# Chov2_main.net
KiCad netlist of a schematic drawn in Altium Designer
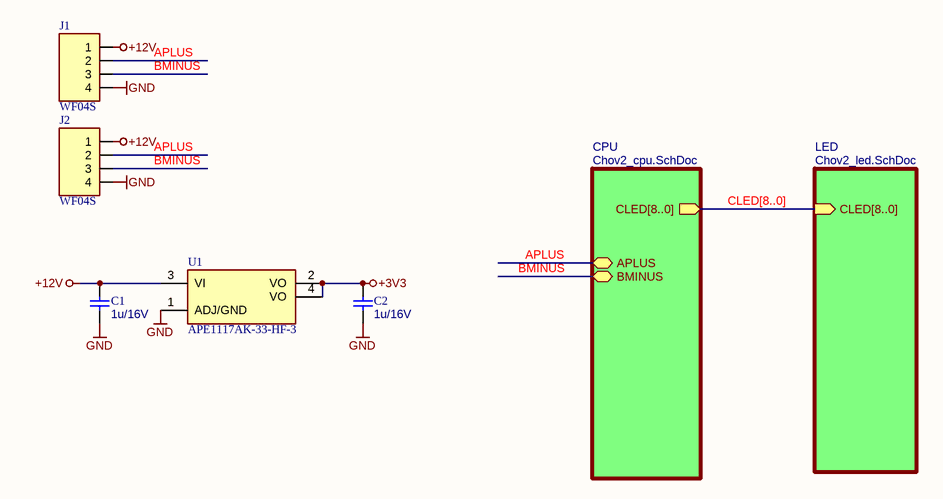
[diagram p0: Chov2_main.SchDoc]

(export (version "E")
  (design (tool "Eeschema 10.0.6"))
  (components
    (comp (ref "C1")
      (value "C0805C105K4RAC")
      (footprint "1206_0805")
      (fields (field (name "OTHERPARAMS") "1u/16V") (field (name "TOLERANCE") "10%"))
      (libsource (lib "Parts") (part "C"))
    )
    (comp (ref "C2")
      (value "C0805C105K4RAC")
      (footprint "1206_0805")
      (fields (field (name "OTHERPARAMS") "1u/16V") (field (name "TOLERANCE") "10%"))
      (libsource (lib "Parts") (part "C"))
    )
    (comp (ref "J1") (value "WF04S") (footprint "WF04S") (libsource (lib "Parts") (part "HEADER4")))
    (comp (ref "J2") (value "WF04S") (footprint "WF04S") (libsource (lib "Parts") (part "HEADER4")))
    (comp (ref "U1")
      (value "APE1117AK-33-HF-3")
      (footprint "SOT-223")
      (libsource (lib "Parts") (part "LM1117IMP"))
    )
  )
  (nets
    (net (code "10") (name "+3V3") (class "Default")
      (node (ref "C2") (pin "1") (pinfunction "1_1") (pintype "passive"))
      (node (ref "U1") (pin "2") (pinfunction "VO_2") (pintype "passive"))
      (node (ref "U1") (pin "4") (pinfunction "VO_4") (pintype "passive"))
    )
    (net (code "11") (name "+12V") (class "Default")
      (node (ref "C1") (pin "1") (pinfunction "1_1") (pintype "passive"))
      (node (ref "J1") (pin "1") (pinfunction "1_1") (pintype "passive"))
      (node (ref "J2") (pin "1") (pinfunction "1_1") (pintype "passive"))
      (node (ref "U1") (pin "3") (pinfunction "VI_3") (pintype "passive"))
    )
    (net (code "12") (name "/APLUS") (class "Default")
      (node (ref "J1") (pin "2") (pinfunction "2_2") (pintype "passive"))
      (node (ref "J2") (pin "2") (pinfunction "2_2") (pintype "passive"))
    )
    (net (code "13") (name "/BMINUS") (class "Default")
      (node (ref "J1") (pin "3") (pinfunction "3_3") (pintype "passive"))
      (node (ref "J2") (pin "3") (pinfunction "3_3") (pintype "passive"))
    )
    (net (code "15") (name "GND") (class "Default")
      (node (ref "C1") (pin "2") (pinfunction "2_2") (pintype "passive"))
      (node (ref "C2") (pin "2") (pinfunction "2_2") (pintype "passive"))
      (node (ref "J1") (pin "4") (pinfunction "4_4") (pintype "passive"))
      (node (ref "J2") (pin "4") (pinfunction "4_4") (pintype "passive"))
      (node (ref "U1") (pin "1") (pinfunction "ADJ/GND_1") (pintype "passive"))
    )
  )
)
